# SilentBotStep.net
KiCad netlist of a schematic drawn in Altium Designer
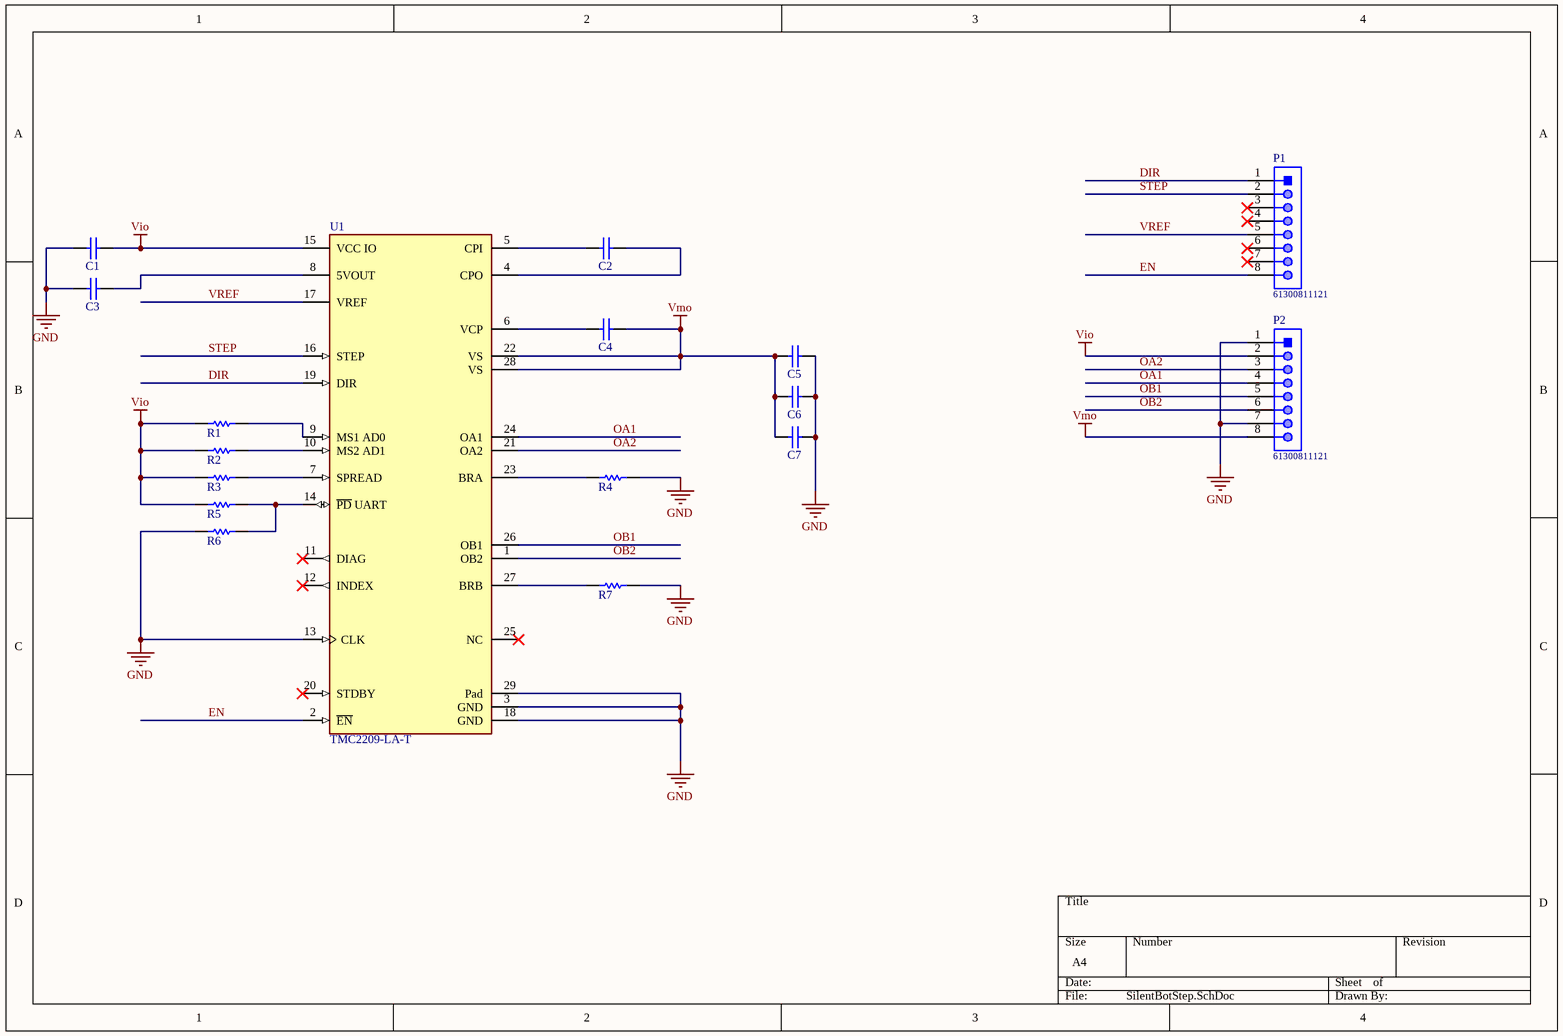
[diagram p0: SilentBotStep.SchDoc]

(export (version "E")
  (design (tool "Eeschema 10.0.6"))
  (components
    (comp (ref "C1")
      (value "GRM155R71H104KE14D")
      (footprint "CAPC1005X55X25LL05T10")
      (description "MURATA - GRM155R71H104KE14D - CAP, MLCC, X7R, 0.1UF, 50V, 0402")
      (fields (field (name "TOLERANCE") "10%") (field (name "VOLTAGE") "50V"))
      (libsource (lib "LTY LLC") (part "CAP"))
    )
    (comp (ref "C2")
      (value "CC0402KRX7R9BB223")
      (footprint "CAPC1005X55X25LL05T10")
      (description "Multilayer Ceramic Capacitors MLCC - SMD/SMT 22K pF 10% 50 Volts")
      (fields (field (name "TOLERANCE") "10%"))
      (libsource (lib "LTY LLC") (part "CAP"))
    )
    (comp (ref "C3")
      (value "GRM155R60J475ME47D")
      (footprint "CAPC1005X55X25LL05T10")
      (description "CAP CER 4.7UF 6.3V X5R 0402")
      (fields (field (name "VOLTAGE") "6.3V") (field (name "TOLERANCE") "20%"))
      (libsource (lib "LTY LLC") (part "CAP"))
    )
    (comp (ref "C4")
      (value "GRM155R71H104KE14D")
      (footprint "CAPC1005X55X25LL05T10")
      (description "MURATA - GRM155R71H104KE14D - CAP, MLCC, X7R, 0.1UF, 50V, 0402")
      (fields (field (name "TOLERANCE") "10%") (field (name "VOLTAGE") "50V"))
      (libsource (lib "LTY LLC") (part "CAP"))
    )
    (comp (ref "C5")
      (value "GRM155R71H104KE14D")
      (footprint "CAPC1005X55X25LL05T10")
      (description "MURATA - GRM155R71H104KE14D - CAP, MLCC, X7R, 0.1UF, 50V, 0402")
      (fields (field (name "TOLERANCE") "10%") (field (name "VOLTAGE") "50V"))
      (libsource (lib "LTY LLC") (part "CAP"))
    )
    (comp (ref "C6")
      (value "GRM155R71H104KE14D")
      (footprint "CAPC1005X55X25LL05T10")
      (description "MURATA - GRM155R71H104KE14D - CAP, MLCC, X7R, 0.1UF, 50V, 0402")
      (fields (field (name "TOLERANCE") "10%") (field (name "VOLTAGE") "50V"))
      (libsource (lib "LTY LLC") (part "CAP"))
    )
    (comp (ref "C7")
      (value "C3216X7R1V106M160AC")
      (footprint "CAPC3216X180X20LL20")
      (fields (field (name "TOLERANCE") "20%"))
      (libsource (lib "LTY LLC") (part "CAP-NP-2"))
    )
    (comp (ref "P1")
      (value "61300811121")
      (footprint "61300811121")
      (description "Board-To-Board Connector, Vertical, Wr-Phd Series, Through Hole, Header, 8, 2.54 Mm")
      (libsource (lib "LTY LLC") (part "WE-CN-1P-M-R8"))
    )
    (comp (ref "P2")
      (value "61300811121")
      (footprint "61300811121")
      (description "Board-To-Board Connector, Vertical, Wr-Phd Series, Through Hole, Header, 8, 2.54 Mm")
      (libsource (lib "LTY LLC") (part "WE-CN-1P-M-R8"))
    )
    (comp (ref "R1")
      (value "RC0402JR-070RL")
      (footprint "RESC1005X40X25LL05T10")
      (description "YAGEO - RC0402JR-070RL. - RES, THICK FILM, 0R, 0.0625W, 0402")
      (fields (field (name "TOLERANCE") "5%"))
      (libsource (lib "LTY LLC") (part "RES"))
    )
    (comp (ref "R2")
      (value "RC0402JR-070RL")
      (footprint "RESC1005X40X25LL05T10")
      (description "YAGEO - RC0402JR-070RL. - RES, THICK FILM, 0R, 0.0625W, 0402")
      (fields (field (name "TOLERANCE") "5%"))
      (libsource (lib "LTY LLC") (part "RES"))
    )
    (comp (ref "R3")
      (value "RC0402JR-070RL")
      (footprint "RESC1005X40X25LL05T10")
      (description "YAGEO - RC0402JR-070RL. - RES, THICK FILM, 0R, 0.0625W, 0402")
      (fields (field (name "TOLERANCE") "5%"))
      (libsource (lib "LTY LLC") (part "RES"))
    )
    (comp (ref "R4")
      (value "RL1220S-R18-F")
      (footprint "RESC2013X50X40LL20T20")
      (description "RES SMD 180 MOHM 1% 1/3W 0805")
      (fields (field (name "TOLERANCE") "1%"))
      (libsource (lib "LTY LLC") (part "RES"))
    )
    (comp (ref "R5")
      (value "RC0402JR-070RL")
      (footprint "RESC1005X40X25LL05T10")
      (description "YAGEO - RC0402JR-070RL. - RES, THICK FILM, 0R, 0.0625W, 0402")
      (fields (field (name "TOLERANCE") "5%"))
      (libsource (lib "LTY LLC") (part "RES"))
    )
    (comp (ref "R6")
      (value "RC0402JR-070RL")
      (footprint "RESC1005X40X25LL05T10")
      (description "YAGEO - RC0402JR-070RL. - RES, THICK FILM, 0R, 0.0625W, 0402")
      (fields (field (name "TOLERANCE") "5%"))
      (libsource (lib "LTY LLC") (part "RES"))
    )
    (comp (ref "R7")
      (value "RL1220S-R18-F")
      (footprint "RESC2013X50X40LL20T20")
      (description "RES SMD 180 MOHM 1% 1/3W 0805")
      (fields (field (name "TOLERANCE") "1%"))
      (libsource (lib "LTY LLC") (part "RES"))
    )
    (comp (ref "U1")
      (value "TMC2209-LA-T")
      (footprint "Trinamic_0_IPC_C")
      (description "Motor Driver, Stepper, QFN-28")
      (libsource (lib "LTY LLC") (part "TMC2209-LA"))
    )
  )
  (nets
    (net (code "1") (name "/DIR") (class "Default")
      (node (ref "P1") (pin "1") (pinfunction "1_1") (pintype "passive"))
      (node (ref "U1") (pin "19") (pinfunction "DIR_19") (pintype "input"))
    )
    (net (code "2") (name "/EN") (class "Default")
      (node (ref "P1") (pin "8") (pinfunction "8_8") (pintype "passive"))
      (node (ref "U1") (pin "2") (pinfunction "~{EN}_2") (pintype "input"))
    )
    (net (code "3") (name "/OA1") (class "Default")
      (node (ref "P2") (pin "4") (pinfunction "4_4") (pintype "passive"))
      (node (ref "U1") (pin "24") (pinfunction "OA1_24") (pintype "passive"))
    )
    (net (code "4") (name "/OA2") (class "Default")
      (node (ref "P2") (pin "3") (pinfunction "3_3") (pintype "passive"))
      (node (ref "U1") (pin "21") (pinfunction "OA2_21") (pintype "passive"))
    )
    (net (code "5") (name "/OB1") (class "Default")
      (node (ref "P2") (pin "5") (pinfunction "5_5") (pintype "passive"))
      (node (ref "U1") (pin "26") (pinfunction "OB1_26") (pintype "passive"))
    )
    (net (code "6") (name "/OB2") (class "Default")
      (node (ref "P2") (pin "6") (pinfunction "6_6") (pintype "passive"))
      (node (ref "U1") (pin "1") (pinfunction "OB2_1") (pintype "passive"))
    )
    (net (code "7") (name "/STEP") (class "Default")
      (node (ref "P1") (pin "2") (pinfunction "2_2") (pintype "passive"))
      (node (ref "U1") (pin "16") (pinfunction "STEP_16") (pintype "input"))
    )
    (net (code "8") (name "/VREF") (class "Default")
      (node (ref "P1") (pin "5") (pinfunction "5_5") (pintype "passive"))
      (node (ref "U1") (pin "17") (pinfunction "VREF_17") (pintype "passive"))
    )
    (net (code "9") (name "GND") (class "Default")
      (node (ref "C1") (pin "1") (pinfunction "1_1") (pintype "passive"))
      (node (ref "C3") (pin "1") (pinfunction "1_1") (pintype "passive"))
      (node (ref "C5") (pin "2") (pinfunction "2_2") (pintype "passive"))
      (node (ref "C6") (pin "2") (pinfunction "2_2") (pintype "passive"))
      (node (ref "C7") (pin "2") (pinfunction "2_2") (pintype "passive"))
      (node (ref "P2") (pin "1") (pinfunction "1_1") (pintype "passive"))
      (node (ref "P2") (pin "7") (pinfunction "7_7") (pintype "passive"))
      (node (ref "R4") (pin "2") (pinfunction "2_2") (pintype "passive"))
      (node (ref "R6") (pin "1") (pinfunction "1_1") (pintype "passive"))
      (node (ref "R7") (pin "2") (pinfunction "2_2") (pintype "passive"))
      (node (ref "U1") (pin "13") (pinfunction "CLK_13") (pintype "input"))
      (node (ref "U1") (pin "18") (pinfunction "GND_18") (pintype "power_in"))
      (node (ref "U1") (pin "29") (pinfunction "Pad_29") (pintype "power_in"))
      (node (ref "U1") (pin "3") (pinfunction "GND_3") (pintype "power_in"))
    )
    (net (code "10") (name "Net-(U1-5VOUT)") (class "Default")
      (node (ref "C3") (pin "2") (pinfunction "2_2") (pintype "passive"))
      (node (ref "U1") (pin "8") (pinfunction "5VOUT_8") (pintype "power_in"))
    )
    (net (code "11") (name "Net-(U1-BRA)") (class "Default")
      (node (ref "R4") (pin "1") (pinfunction "1_1") (pintype "passive"))
      (node (ref "U1") (pin "23") (pinfunction "BRA_23") (pintype "passive"))
    )
    (net (code "12") (name "Net-(U1-BRB)") (class "Default")
      (node (ref "R7") (pin "1") (pinfunction "1_1") (pintype "passive"))
      (node (ref "U1") (pin "27") (pinfunction "BRB_27") (pintype "passive"))
    )
    (net (code "13") (name "Net-(U1-CPI)") (class "Default")
      (node (ref "C2") (pin "1") (pinfunction "1_1") (pintype "passive"))
      (node (ref "U1") (pin "5") (pinfunction "CPI_5") (pintype "passive"))
    )
    (net (code "14") (name "Net-(U1-CPO)") (class "Default")
      (node (ref "C2") (pin "2") (pinfunction "2_2") (pintype "passive"))
      (node (ref "U1") (pin "4") (pinfunction "CPO_4") (pintype "passive"))
    )
    (net (code "15") (name "Net-(U1-MS1_AD0)") (class "Default")
      (node (ref "R1") (pin "2") (pinfunction "2_2") (pintype "passive"))
      (node (ref "U1") (pin "9") (pinfunction "MS1_AD0_9") (pintype "input"))
    )
    (net (code "16") (name "Net-(U1-MS2_AD1)") (class "Default")
      (node (ref "R2") (pin "2") (pinfunction "2_2") (pintype "passive"))
      (node (ref "U1") (pin "10") (pinfunction "MS2_AD1_10") (pintype "input"))
    )
    (net (code "17") (name "Net-(U1-SPREAD)") (class "Default")
      (node (ref "R3") (pin "2") (pinfunction "2_2") (pintype "passive"))
      (node (ref "U1") (pin "7") (pinfunction "SPREAD_7") (pintype "input"))
    )
    (net (code "18") (name "Net-(U1-VCP)") (class "Default")
      (node (ref "C4") (pin "1") (pinfunction "1_1") (pintype "passive"))
      (node (ref "U1") (pin "6") (pinfunction "VCP_6") (pintype "power_in"))
    )
    (net (code "19") (name "Net-(U1-~{PD}_UART)") (class "Default")
      (node (ref "R5") (pin "2") (pinfunction "2_2") (pintype "passive"))
      (node (ref "R6") (pin "2") (pinfunction "2_2") (pintype "passive"))
      (node (ref "U1") (pin "14") (pinfunction "~{PD}_UART_14") (pintype "bidirectional"))
    )
    (net (code "20") (name "Vio") (class "Default")
      (node (ref "C1") (pin "2") (pinfunction "2_2") (pintype "passive"))
      (node (ref "P2") (pin "2") (pinfunction "2_2") (pintype "passive"))
      (node (ref "R1") (pin "1") (pinfunction "1_1") (pintype "passive"))
      (node (ref "R2") (pin "1") (pinfunction "1_1") (pintype "passive"))
      (node (ref "R3") (pin "1") (pinfunction "1_1") (pintype "passive"))
      (node (ref "R5") (pin "1") (pinfunction "1_1") (pintype "passive"))
      (node (ref "U1") (pin "15") (pinfunction "VCC_IO_15") (pintype "power_in"))
    )
    (net (code "21") (name "Vmo") (class "Default")
      (node (ref "C4") (pin "2") (pinfunction "2_2") (pintype "passive"))
      (node (ref "C5") (pin "1") (pinfunction "1_1") (pintype "passive"))
      (node (ref "C6") (pin "1") (pinfunction "1_1") (pintype "passive"))
      (node (ref "C7") (pin "1") (pinfunction "1_1") (pintype "passive"))
      (node (ref "P2") (pin "8") (pinfunction "8_8") (pintype "passive"))
      (node (ref "U1") (pin "22") (pinfunction "VS_22") (pintype "power_in"))
      (node (ref "U1") (pin "28") (pinfunction "VS_28") (pintype "power_in"))
    )
    (net (code "22") (name "unconnected-(P1-Pad3)") (class "Default")
      (node (ref "P1") (pin "3") (pinfunction "3_3") (pintype "passive+no_connect"))
    )
    (net (code "23") (name "unconnected-(P1-Pad4)") (class "Default")
      (node (ref "P1") (pin "4") (pinfunction "4_4") (pintype "passive+no_connect"))
    )
    (net (code "24") (name "unconnected-(P1-Pad6)") (class "Default")
      (node (ref "P1") (pin "6") (pinfunction "6_6") (pintype "passive+no_connect"))
    )
    (net (code "25") (name "unconnected-(P1-Pad7)") (class "Default")
      (node (ref "P1") (pin "7") (pinfunction "7_7") (pintype "passive+no_connect"))
    )
    (net (code "26") (name "unconnected-(U1-DIAG-Pad11)") (class "Default")
      (node (ref "U1") (pin "11") (pinfunction "DIAG_11") (pintype "output+no_connect"))
    )
    (net (code "27") (name "unconnected-(U1-INDEX-Pad12)") (class "Default")
      (node (ref "U1") (pin "12") (pinfunction "INDEX_12") (pintype "output+no_connect"))
    )
    (net (code "28") (name "unconnected-(U1-NC-Pad25)") (class "Default")
      (node (ref "U1") (pin "25") (pinfunction "NC_25") (pintype "passive+no_connect"))
    )
    (net (code "29") (name "unconnected-(U1-STDBY-Pad20)") (class "Default")
      (node (ref "U1") (pin "20") (pinfunction "STDBY_20") (pintype "input+no_connect"))
    )
  )
)
